# ME433_SCH1.net
KiCad netlist of a schematic drawn in EAGLE
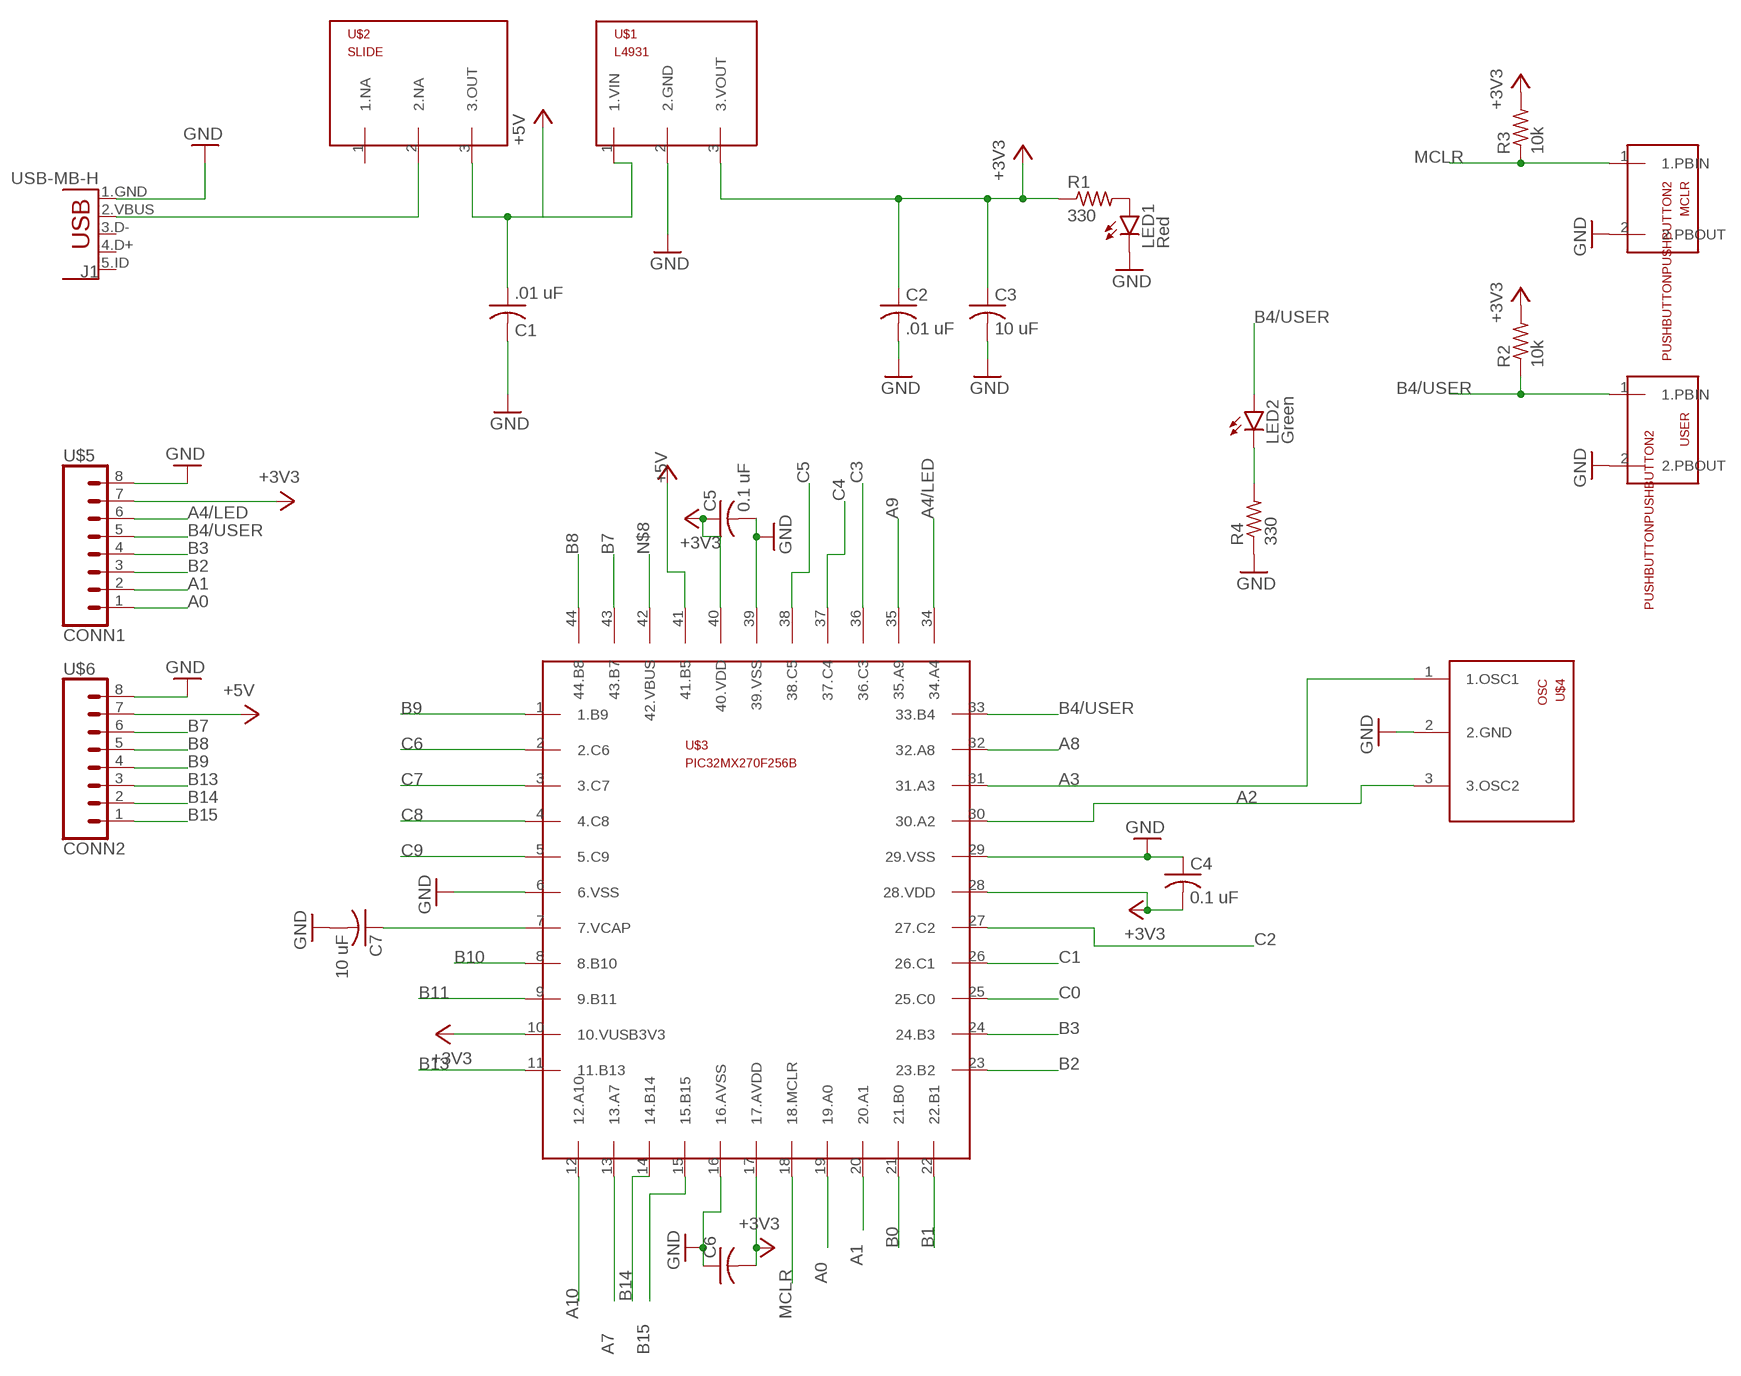
[diagram p0: schematic, sheet 1]

(export (version "E")
  (design (tool "Eeschema 10.0.6"))
  (components
    (comp (ref "C1")
      (value ".01 uF")
      (footprint "eagle-import:C050-024X044")
      (libsource (lib "eagle-import") (part "C-US050-024X044"))
    )
    (comp (ref "C2")
      (value ".01 uF")
      (footprint "eagle-import:C050-024X044")
      (libsource (lib "eagle-import") (part "C-US050-024X044"))
    )
    (comp (ref "C3")
      (value "10 uF")
      (footprint "eagle-import:C050-024X044")
      (libsource (lib "eagle-import") (part "C-US050-024X044"))
    )
    (comp (ref "C4")
      (value "0.1 uF")
      (footprint "eagle-import:C050-024X044")
      (libsource (lib "eagle-import") (part "C-US050-024X044"))
    )
    (comp (ref "C5")
      (value "0.1 uF")
      (footprint "eagle-import:C050-024X044")
      (libsource (lib "eagle-import") (part "C-US050-024X044"))
    )
    (comp (ref "C6")
      (value "C-US050-024X044")
      (footprint "eagle-import:C050-024X044")
      (libsource (lib "eagle-import") (part "C-US050-024X044"))
    )
    (comp (ref "C7")
      (value "10 uF")
      (footprint "eagle-import:C050-024X044")
      (libsource (lib "eagle-import") (part "C-US050-024X044"))
    )
    (comp (ref "J1")
      (value "USB-MB-H")
      (footprint "eagle-import:USB-MB-H")
      (libsource (lib "eagle-import") (part "USB-MB-H"))
    )
    (comp (ref "LED1")
      (value "Red")
      (footprint "eagle-import:LED3MM")
      (libsource (lib "eagle-import") (part "LED3MM"))
    )
    (comp (ref "LED2")
      (value "Green")
      (footprint "eagle-import:LED3MM")
      (libsource (lib "eagle-import") (part "LED3MM"))
    )
    (comp (ref "MCLR")
      (value "PUSHBUTTONPUSHBUTTON2")
      (footprint "eagle-import:PUSHBUTTON")
      (libsource (lib "eagle-import") (part "PUSHBUTTONPUSHBUTTON2"))
    )
    (comp (ref "R1")
      (value "330")
      (footprint "eagle-import:0207_10")
      (libsource (lib "eagle-import") (part "R-US_0207/10"))
    )
    (comp (ref "R2")
      (value "10k")
      (footprint "eagle-import:0207_10")
      (libsource (lib "eagle-import") (part "R-US_0207/10"))
    )
    (comp (ref "R3")
      (value "10k")
      (footprint "eagle-import:0207_10")
      (libsource (lib "eagle-import") (part "R-US_0207/10"))
    )
    (comp (ref "R4")
      (value "330")
      (footprint "eagle-import:0207_10")
      (libsource (lib "eagle-import") (part "R-US_0207/10"))
    )
    (comp (ref "U$1")
      (value "L4931")
      (footprint "eagle-import:TO92")
      (libsource (lib "eagle-import") (part "L4931"))
    )
    (comp (ref "U$2")
      (value "SLIDE")
      (footprint "eagle-import:SLIDE")
      (libsource (lib "eagle-import") (part "SLIDE"))
    )
    (comp (ref "U$3")
      (value "PIC32MX270F256B")
      (footprint "eagle-import:TQFP44")
      (libsource (lib "eagle-import") (part "PIC32MX270F256B"))
    )
    (comp (ref "U$4")
      (value "OSC")
      (footprint "eagle-import:OSC")
      (libsource (lib "eagle-import") (part "OSC"))
    )
    (comp (ref "U$5")
      (value "CONN1")
      (footprint "eagle-import:CONN1")
      (libsource (lib "eagle-import") (part "CONN1"))
    )
    (comp (ref "U$6")
      (value "CONN2")
      (footprint "eagle-import:CONN1")
      (libsource (lib "eagle-import") (part "CONN2"))
    )
    (comp (ref "USER")
      (value "PUSHBUTTONPUSHBUTTON2")
      (footprint "eagle-import:PUSHBUTTON")
      (libsource (lib "eagle-import") (part "PUSHBUTTONPUSHBUTTON2"))
    )
  )
  (nets
    (net (code "1") (name "+3V3") (class "Default")
      (node (ref "C2") (pin "1") (pinfunction "1_1") (pintype "passive"))
      (node (ref "C3") (pin "1") (pinfunction "1_1") (pintype "passive"))
      (node (ref "C4") (pin "2") (pinfunction "2_2") (pintype "passive"))
      (node (ref "C5") (pin "1") (pinfunction "1_1") (pintype "passive"))
      (node (ref "C6") (pin "2") (pinfunction "2_2") (pintype "passive"))
      (node (ref "R1") (pin "1") (pinfunction "1_1") (pintype "passive"))
      (node (ref "R2") (pin "2") (pinfunction "2_2") (pintype "passive"))
      (node (ref "R3") (pin "2") (pinfunction "2_2") (pintype "passive"))
      (node (ref "U$1") (pin "3") (pinfunction "3.VOUT_3") (pintype "bidirectional"))
      (node (ref "U$3") (pin "10") (pinfunction "10.VUSB3V3_10") (pintype "bidirectional"))
      (node (ref "U$3") (pin "17") (pinfunction "17.AVDD_17") (pintype "bidirectional"))
      (node (ref "U$3") (pin "28") (pinfunction "28.VDD_28") (pintype "bidirectional"))
      (node (ref "U$3") (pin "40") (pinfunction "40.VDD_40") (pintype "bidirectional"))
      (node (ref "U$5") (pin "7") (pinfunction "7.3V3_7") (pintype "passive"))
    )
    (net (code "2") (name "+5V") (class "Default")
      (node (ref "C1") (pin "1") (pinfunction "1_1") (pintype "passive"))
      (node (ref "U$1") (pin "1") (pinfunction "1.VIN_1") (pintype "bidirectional"))
      (node (ref "U$2") (pin "3") (pinfunction "3.OUT_3") (pintype "bidirectional"))
      (node (ref "U$3") (pin "41") (pinfunction "41.B5_41") (pintype "bidirectional"))
      (node (ref "U$6") (pin "7") (pinfunction "7.5V_7") (pintype "passive"))
    )
    (net (code "3") (name "/A0") (class "Default")
      (node (ref "U$3") (pin "19") (pinfunction "19.A0_19") (pintype "bidirectional"))
      (node (ref "U$5") (pin "1") (pinfunction "1.A0_1") (pintype "passive"))
    )
    (net (code "4") (name "/A1") (class "Default")
      (node (ref "U$3") (pin "20") (pinfunction "20.A1_20") (pintype "bidirectional"))
      (node (ref "U$5") (pin "2") (pinfunction "2.A1_2") (pintype "passive"))
    )
    (net (code "5") (name "/A2") (class "Default")
      (node (ref "U$3") (pin "30") (pinfunction "30.A2_30") (pintype "bidirectional"))
      (node (ref "U$4") (pin "3") (pinfunction "3.OSC2_3") (pintype "bidirectional"))
    )
    (net (code "6") (name "/A3") (class "Default")
      (node (ref "U$3") (pin "31") (pinfunction "31.A3_31") (pintype "bidirectional"))
      (node (ref "U$4") (pin "1") (pinfunction "1.OSC1_1") (pintype "bidirectional"))
    )
    (net (code "7") (name "/A4{slash}LED") (class "Default")
      (node (ref "U$3") (pin "34") (pinfunction "34.A4_34") (pintype "bidirectional"))
      (node (ref "U$5") (pin "6") (pinfunction "6.A4_6") (pintype "passive"))
    )
    (net (code "8") (name "/A7") (class "Default")
      (node (ref "U$3") (pin "13") (pinfunction "13.A7_13") (pintype "bidirectional"))
    )
    (net (code "9") (name "/A8") (class "Default")
      (node (ref "U$3") (pin "32") (pinfunction "32.A8_32") (pintype "bidirectional"))
    )
    (net (code "10") (name "/A9") (class "Default")
      (node (ref "U$3") (pin "35") (pinfunction "35.A9_35") (pintype "bidirectional"))
    )
    (net (code "11") (name "/A10") (class "Default")
      (node (ref "U$3") (pin "12") (pinfunction "12.A10_12") (pintype "bidirectional"))
    )
    (net (code "12") (name "/B0") (class "Default")
      (node (ref "U$3") (pin "21") (pinfunction "21.B0_21") (pintype "bidirectional"))
    )
    (net (code "13") (name "/B1") (class "Default")
      (node (ref "U$3") (pin "22") (pinfunction "22.B1_22") (pintype "bidirectional"))
    )
    (net (code "14") (name "/B2") (class "Default")
      (node (ref "U$3") (pin "23") (pinfunction "23.B2_23") (pintype "bidirectional"))
      (node (ref "U$5") (pin "3") (pinfunction "3.B2_3") (pintype "passive"))
    )
    (net (code "15") (name "/B3") (class "Default")
      (node (ref "U$3") (pin "24") (pinfunction "24.B3_24") (pintype "bidirectional"))
      (node (ref "U$5") (pin "4") (pinfunction "4.B3_4") (pintype "passive"))
    )
    (net (code "16") (name "/B4{slash}USER") (class "Default")
      (node (ref "LED2") (pin "A") (pinfunction "A_A") (pintype "passive"))
      (node (ref "R2") (pin "1") (pinfunction "1_1") (pintype "passive"))
      (node (ref "U$3") (pin "33") (pinfunction "33.B4_33") (pintype "bidirectional"))
      (node (ref "U$5") (pin "5") (pinfunction "5.B4_5") (pintype "passive"))
      (node (ref "USER") (pin "1") (pinfunction "1.PBIN_1") (pintype "bidirectional"))
    )
    (net (code "17") (name "/B7") (class "Default")
      (node (ref "U$3") (pin "43") (pinfunction "43.B7_43") (pintype "bidirectional"))
      (node (ref "U$6") (pin "6") (pinfunction "6.B7_6") (pintype "passive"))
    )
    (net (code "18") (name "/B8") (class "Default")
      (node (ref "U$3") (pin "44") (pinfunction "44.B8_44") (pintype "bidirectional"))
      (node (ref "U$6") (pin "5") (pinfunction "5.B8_5") (pintype "passive"))
    )
    (net (code "19") (name "/B9") (class "Default")
      (node (ref "U$3") (pin "1") (pinfunction "1.B9_1") (pintype "bidirectional"))
      (node (ref "U$6") (pin "4") (pinfunction "4.B9_4") (pintype "passive"))
    )
    (net (code "20") (name "/B10") (class "Default")
      (node (ref "U$3") (pin "8") (pinfunction "8.B10_8") (pintype "bidirectional"))
    )
    (net (code "21") (name "/B11") (class "Default")
      (node (ref "U$3") (pin "9") (pinfunction "9.B11_9") (pintype "bidirectional"))
    )
    (net (code "22") (name "/B13") (class "Default")
      (node (ref "U$3") (pin "11") (pinfunction "11.B13_11") (pintype "bidirectional"))
      (node (ref "U$6") (pin "3") (pinfunction "3.B13_3") (pintype "passive"))
    )
    (net (code "23") (name "/B14") (class "Default")
      (node (ref "U$3") (pin "14") (pinfunction "14.B14_14") (pintype "bidirectional"))
      (node (ref "U$6") (pin "2") (pinfunction "2.B14_2") (pintype "passive"))
    )
    (net (code "24") (name "/B15") (class "Default")
      (node (ref "U$3") (pin "15") (pinfunction "15.B15_15") (pintype "bidirectional"))
      (node (ref "U$6") (pin "1") (pinfunction "1.B15_1") (pintype "passive"))
    )
    (net (code "25") (name "/C0") (class "Default")
      (node (ref "U$3") (pin "25") (pinfunction "25.C0_25") (pintype "bidirectional"))
    )
    (net (code "26") (name "/C1") (class "Default")
      (node (ref "U$3") (pin "26") (pinfunction "26.C1_26") (pintype "bidirectional"))
    )
    (net (code "27") (name "/C2") (class "Default")
      (node (ref "U$3") (pin "27") (pinfunction "27.C2_27") (pintype "bidirectional"))
    )
    (net (code "28") (name "/C3") (class "Default")
      (node (ref "U$3") (pin "36") (pinfunction "36.C3_36") (pintype "bidirectional"))
    )
    (net (code "29") (name "/C4") (class "Default")
      (node (ref "U$3") (pin "37") (pinfunction "37.C4_37") (pintype "bidirectional"))
    )
    (net (code "30") (name "/C5") (class "Default")
      (node (ref "U$3") (pin "38") (pinfunction "38.C5_38") (pintype "bidirectional"))
    )
    (net (code "31") (name "/C6") (class "Default")
      (node (ref "U$3") (pin "2") (pinfunction "2.C6_2") (pintype "bidirectional"))
    )
    (net (code "32") (name "/C7") (class "Default")
      (node (ref "U$3") (pin "3") (pinfunction "3.C7_3") (pintype "bidirectional"))
    )
    (net (code "33") (name "/C8") (class "Default")
      (node (ref "U$3") (pin "4") (pinfunction "4.C8_4") (pintype "bidirectional"))
    )
    (net (code "34") (name "/C9") (class "Default")
      (node (ref "U$3") (pin "5") (pinfunction "5.C9_5") (pintype "bidirectional"))
    )
    (net (code "35") (name "/MCLR") (class "Default")
      (node (ref "MCLR") (pin "1") (pinfunction "1.PBIN_1") (pintype "bidirectional"))
      (node (ref "R3") (pin "1") (pinfunction "1_1") (pintype "passive"))
      (node (ref "U$3") (pin "18") (pinfunction "18.MCLR_18") (pintype "bidirectional"))
    )
    (net (code "36") (name "/N$8") (class "Default")
      (node (ref "U$3") (pin "42") (pinfunction "42.VBUS_42") (pintype "bidirectional"))
    )
    (net (code "37") (name "GND") (class "Default")
      (node (ref "C1") (pin "2") (pinfunction "2_2") (pintype "passive"))
      (node (ref "C2") (pin "2") (pinfunction "2_2") (pintype "passive"))
      (node (ref "C3") (pin "2") (pinfunction "2_2") (pintype "passive"))
      (node (ref "C4") (pin "1") (pinfunction "1_1") (pintype "passive"))
      (node (ref "C5") (pin "2") (pinfunction "2_2") (pintype "passive"))
      (node (ref "C6") (pin "1") (pinfunction "1_1") (pintype "passive"))
      (node (ref "C7") (pin "2") (pinfunction "2_2") (pintype "passive"))
      (node (ref "J1") (pin "1.GND") (pinfunction "1.GND_1.GND") (pintype "bidirectional"))
      (node (ref "LED1") (pin "K") (pinfunction "C_K") (pintype "passive"))
      (node (ref "MCLR") (pin "2") (pinfunction "2.PBOUT_2") (pintype "bidirectional"))
      (node (ref "R4") (pin "1") (pinfunction "1_1") (pintype "passive"))
      (node (ref "U$1") (pin "2") (pinfunction "2.GND_2") (pintype "bidirectional"))
      (node (ref "U$3") (pin "16") (pinfunction "16.AVSS_16") (pintype "bidirectional"))
      (node (ref "U$3") (pin "29") (pinfunction "29.VSS_29") (pintype "bidirectional"))
      (node (ref "U$3") (pin "39") (pinfunction "39.VSS_39") (pintype "bidirectional"))
      (node (ref "U$3") (pin "6") (pinfunction "6.VSS_6") (pintype "bidirectional"))
      (node (ref "U$4") (pin "2") (pinfunction "2.GND_2") (pintype "bidirectional"))
      (node (ref "U$5") (pin "8") (pinfunction "8.GND_8") (pintype "passive"))
      (node (ref "U$6") (pin "8") (pinfunction "8.GND_8") (pintype "passive"))
      (node (ref "USER") (pin "2") (pinfunction "2.PBOUT_2") (pintype "bidirectional"))
    )
    (net (code "38") (name "Net-(LED1-PadA)") (class "Default")
      (node (ref "LED1") (pin "A") (pinfunction "A_A") (pintype "passive"))
      (node (ref "R1") (pin "2") (pinfunction "2_2") (pintype "passive"))
    )
    (net (code "39") (name "Net-(LED2-C)") (class "Default")
      (node (ref "LED2") (pin "K") (pinfunction "C_K") (pintype "passive"))
      (node (ref "R4") (pin "2") (pinfunction "2_2") (pintype "passive"))
    )
    (net (code "40") (name "Net-(U$2-2.NA)") (class "Default")
      (node (ref "J1") (pin "2.VBUS") (pinfunction "2.VBUS_2.VBUS") (pintype "bidirectional"))
      (node (ref "U$2") (pin "2") (pinfunction "2.NA_2") (pintype "bidirectional"))
    )
    (net (code "41") (name "Net-(U$3-7.VCAP)") (class "Default")
      (node (ref "C7") (pin "1") (pinfunction "1_1") (pintype "passive"))
      (node (ref "U$3") (pin "7") (pinfunction "7.VCAP_7") (pintype "bidirectional"))
    )
    (net (code "42") (name "unconnected-(J1-Pad3.D-)") (class "Default")
      (node (ref "J1") (pin "3.D-") (pinfunction "3.D-_3.D-") (pintype "bidirectional"))
    )
    (net (code "43") (name "unconnected-(J1-Pad4.D+)") (class "Default")
      (node (ref "J1") (pin "4.D+") (pinfunction "4.D+_4.D+") (pintype "bidirectional"))
    )
    (net (code "44") (name "unconnected-(J1-Pad5.ID)") (class "Default")
      (node (ref "J1") (pin "5.ID") (pinfunction "5.ID_5.ID") (pintype "bidirectional"))
    )
    (net (code "45") (name "unconnected-(U$2-1.NA-Pad1)") (class "Default")
      (node (ref "U$2") (pin "1") (pinfunction "1.NA_1") (pintype "bidirectional"))
    )
  )
)
